# amplifier__6_1_Channel_v0001.net
KiCad netlist of a schematic drawn in EAGLE
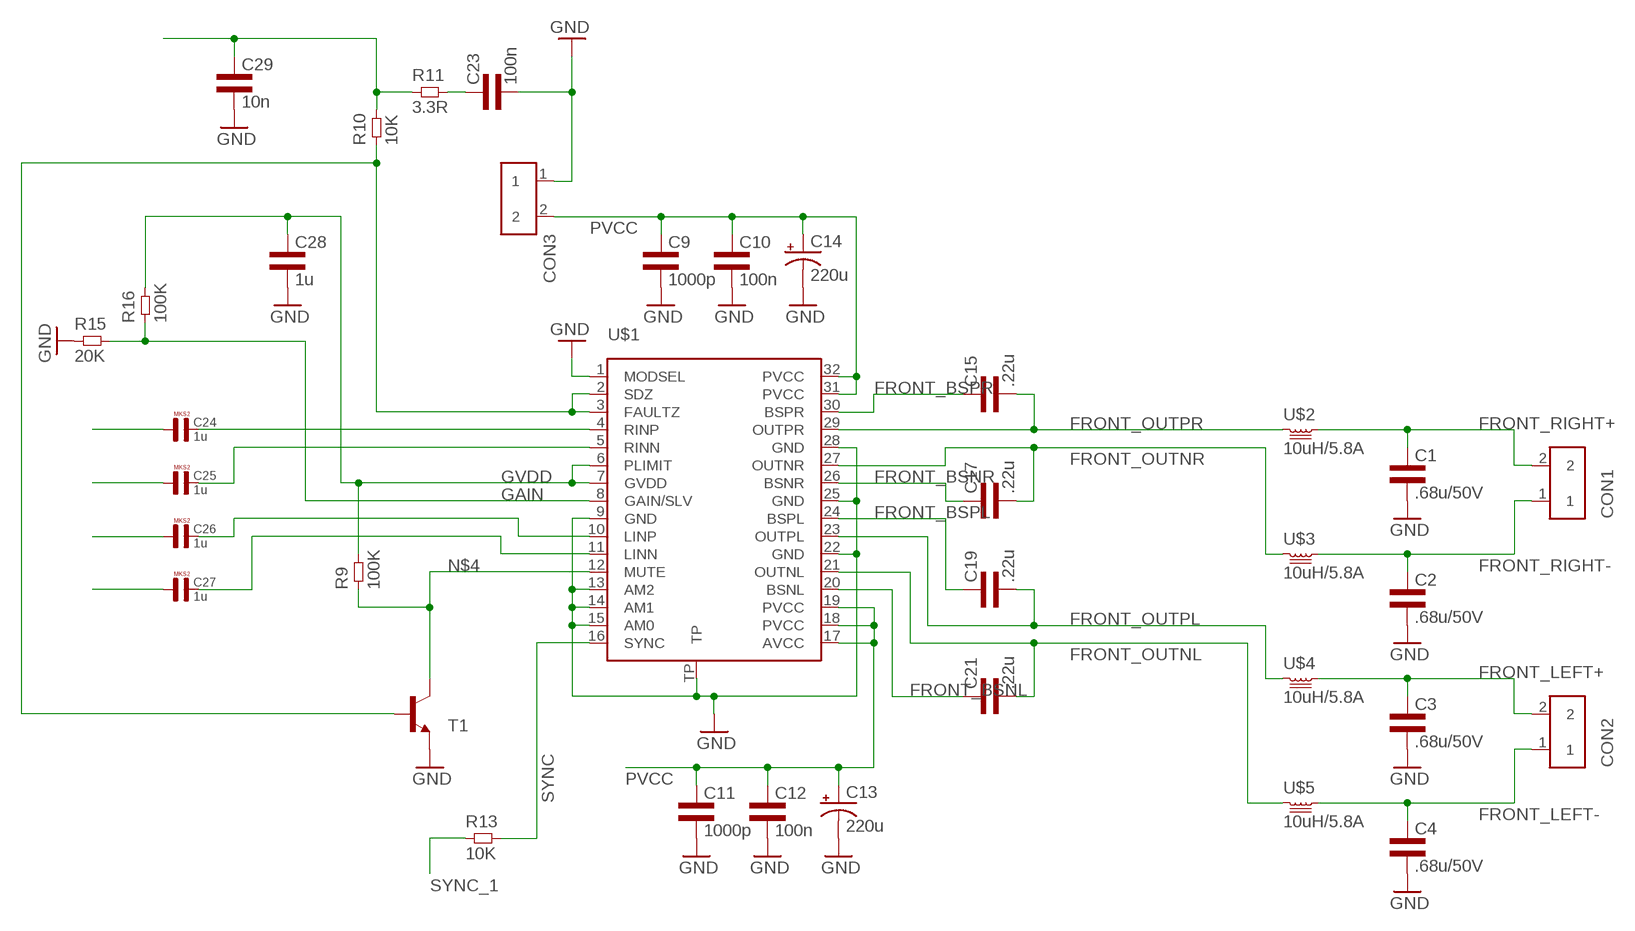
[diagram p0: schematic, sheet 1]
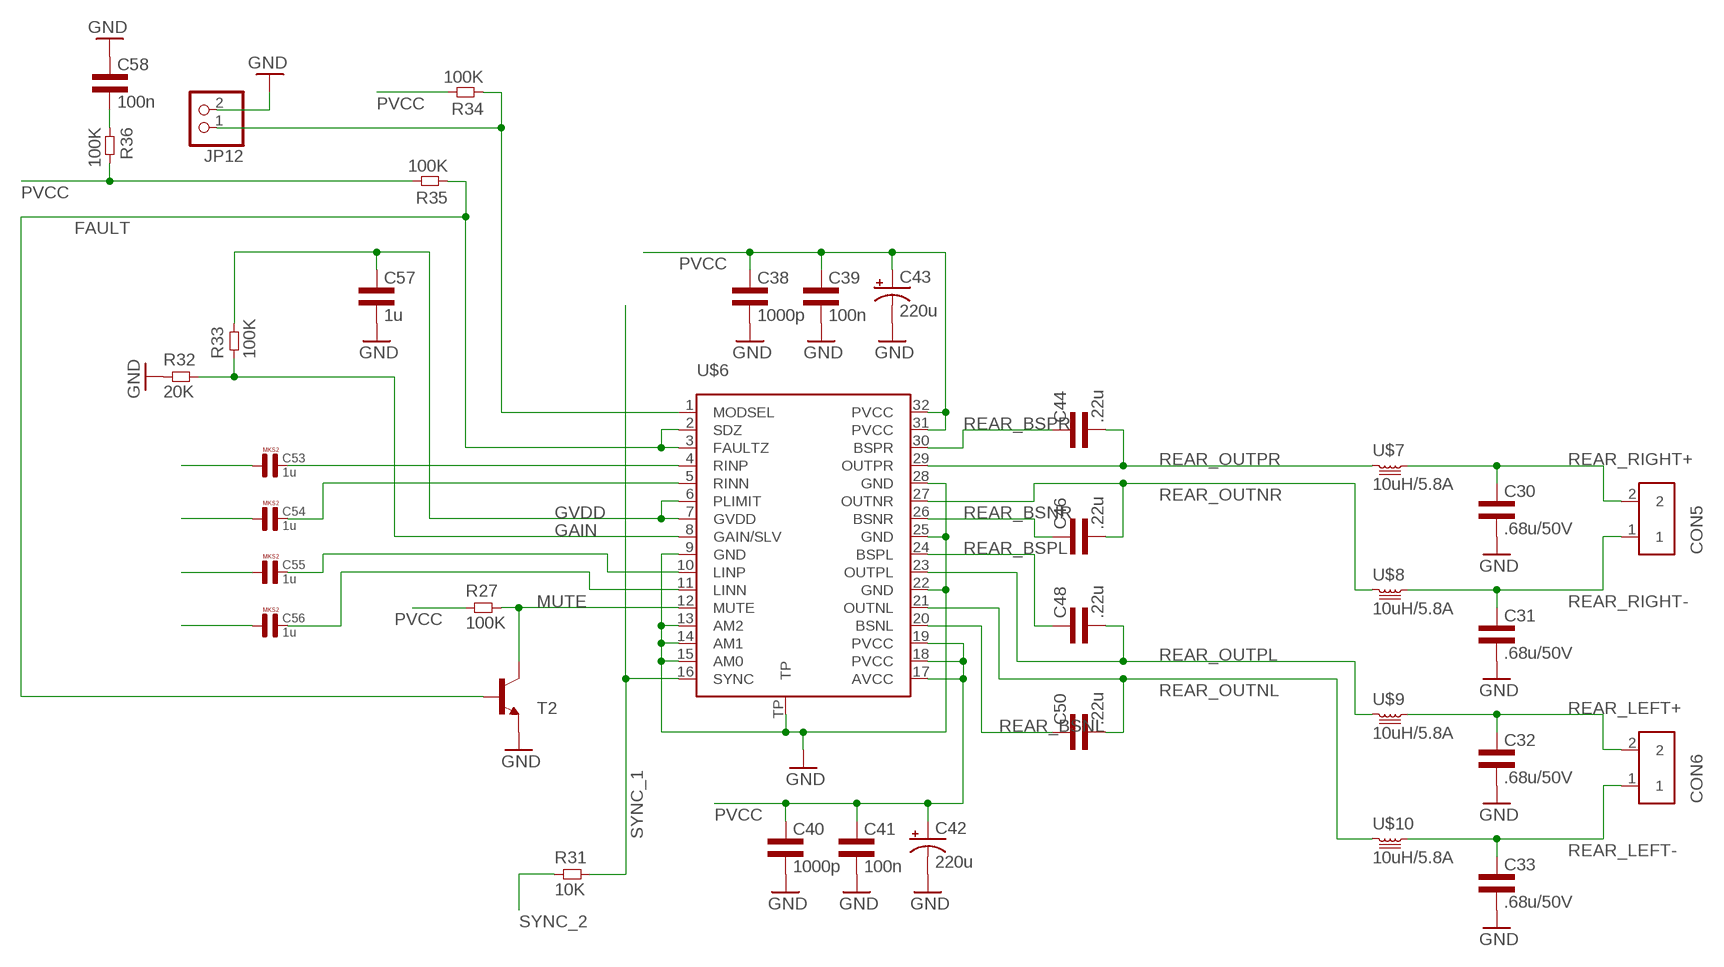
[diagram p1: schematic, sheet 2]
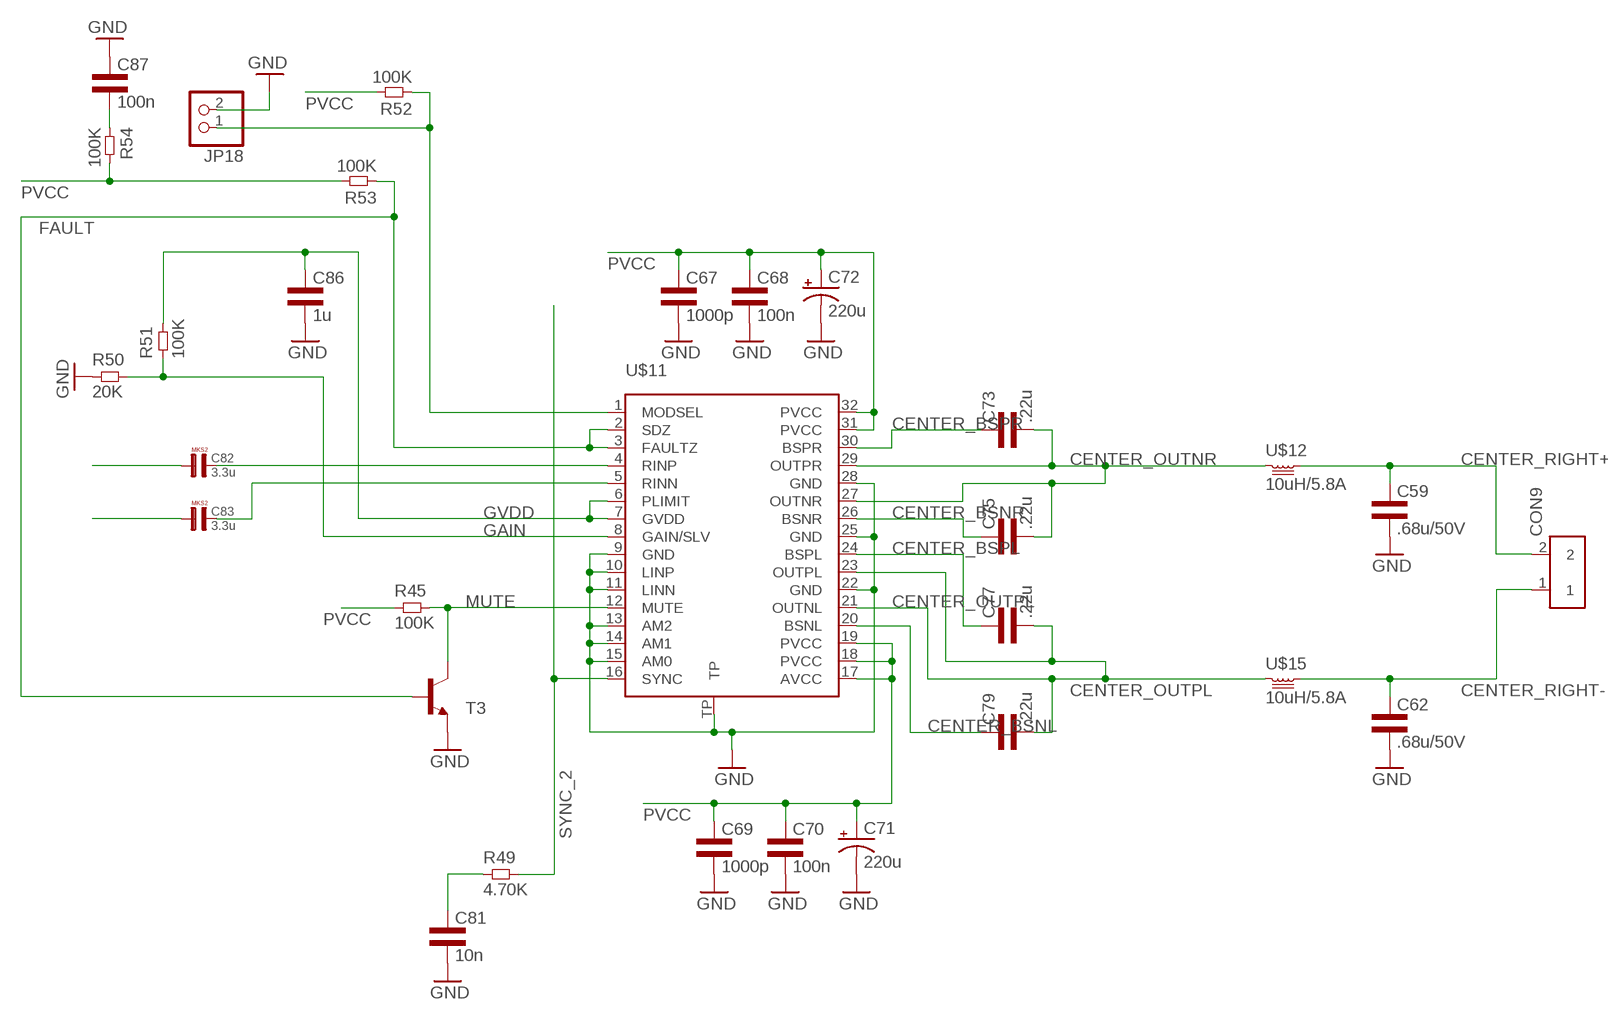
[diagram p2: schematic, sheet 3]

(export (version "E")
  (design (tool "Eeschema 10.0.6"))
  (components
    (comp (ref "C30")
      (value ".68u/50V")
      (footprint "eagle-import:1206L3")
      (libsource (lib "eagle-import") (part "CAP1206L3"))
    )
    (comp (ref "C31")
      (value ".68u/50V")
      (footprint "eagle-import:1206L3")
      (libsource (lib "eagle-import") (part "CAP1206L3"))
    )
    (comp (ref "C32")
      (value ".68u/50V")
      (footprint "eagle-import:1206L3")
      (libsource (lib "eagle-import") (part "CAP1206L3"))
    )
    (comp (ref "C33")
      (value ".68u/50V")
      (footprint "eagle-import:1206L3")
      (libsource (lib "eagle-import") (part "CAP1206L3"))
    )
    (comp (ref "C38")
      (value "1000p")
      (footprint "eagle-import:0603L3")
      (libsource (lib "eagle-import") (part "CAP0603L3"))
    )
    (comp (ref "C39")
      (value "100n")
      (footprint "eagle-import:0603L3")
      (libsource (lib "eagle-import") (part "CAP0603L3"))
    )
    (comp (ref "C40")
      (value "1000p")
      (footprint "eagle-import:0603L3")
      (libsource (lib "eagle-import") (part "CAP0603L3"))
    )
    (comp (ref "C41")
      (value "100n")
      (footprint "eagle-import:0603L3")
      (libsource (lib "eagle-import") (part "CAP0603L3"))
    )
    (comp (ref "C42")
      (value "220u")
      (footprint "eagle-import:PANASONIC_G")
      (libsource (lib "eagle-import") (part "CPOL-USG"))
    )
    (comp (ref "C43")
      (value "220u")
      (footprint "eagle-import:PANASONIC_G")
      (libsource (lib "eagle-import") (part "CPOL-USG"))
    )
    (comp (ref "C44")
      (value ".22u")
      (footprint "eagle-import:0603L3")
      (libsource (lib "eagle-import") (part "CAP0603L3"))
    )
    (comp (ref "C46")
      (value ".22u")
      (footprint "eagle-import:0603L3")
      (libsource (lib "eagle-import") (part "CAP0603L3"))
    )
    (comp (ref "C48")
      (value ".22u")
      (footprint "eagle-import:0603L3")
      (libsource (lib "eagle-import") (part "CAP0603L3"))
    )
    (comp (ref "C50")
      (value ".22u")
      (footprint "eagle-import:0603L3")
      (libsource (lib "eagle-import") (part "CAP0603L3"))
    )
    (comp (ref "C53")
      (value "1u")
      (footprint "eagle-import:R5B8K5")
      (libsource (lib "eagle-import") (part "3,3µF"))
    )
    (comp (ref "C54")
      (value "1u")
      (footprint "eagle-import:R5B8K5")
      (libsource (lib "eagle-import") (part "3,3µF"))
    )
    (comp (ref "C55")
      (value "1u")
      (footprint "eagle-import:R5B8K5")
      (libsource (lib "eagle-import") (part "3,3µF"))
    )
    (comp (ref "C56")
      (value "1u")
      (footprint "eagle-import:R5B8K5")
      (libsource (lib "eagle-import") (part "3,3µF"))
    )
    (comp (ref "C57")
      (value "1u")
      (footprint "eagle-import:0603L3")
      (libsource (lib "eagle-import") (part "CAP0603L3"))
    )
    (comp (ref "C58")
      (value "100n")
      (footprint "eagle-import:0603L3")
      (libsource (lib "eagle-import") (part "CAP0603L3"))
    )
    (comp (ref "CON5")
      (value "TERM_BLOCK_2")
      (footprint "eagle-import:TERM_BLOCK_2")
      (libsource (lib "eagle-import") (part "TERM_BLOCK_2"))
    )
    (comp (ref "CON6")
      (value "TERM_BLOCK_2")
      (footprint "eagle-import:TERM_BLOCK_2")
      (libsource (lib "eagle-import") (part "TERM_BLOCK_2"))
    )
    (comp (ref "JP12")
      (value "PINHD-1X2")
      (footprint "eagle-import:1X02")
      (libsource (lib "eagle-import") (part "PINHD-1X2"))
    )
    (comp (ref "R27")
      (value "100K")
      (footprint "eagle-import:0603L3")
      (libsource (lib "eagle-import") (part "RES0603L3"))
    )
    (comp (ref "R31")
      (value "10K")
      (footprint "eagle-import:0603L3")
      (libsource (lib "eagle-import") (part "RES0603L3"))
    )
    (comp (ref "R32")
      (value "20K")
      (footprint "eagle-import:0603L3")
      (libsource (lib "eagle-import") (part "RES0603L3"))
    )
    (comp (ref "R33")
      (value "100K")
      (footprint "eagle-import:0603L3")
      (libsource (lib "eagle-import") (part "RES0603L3"))
    )
    (comp (ref "R34")
      (value "100K")
      (footprint "eagle-import:0603L3")
      (libsource (lib "eagle-import") (part "RES0603L3"))
    )
    (comp (ref "R35")
      (value "100K")
      (footprint "eagle-import:0603L3")
      (libsource (lib "eagle-import") (part "RES0603L3"))
    )
    (comp (ref "R36")
      (value "100K")
      (footprint "eagle-import:0603L3")
      (libsource (lib "eagle-import") (part "RES0603L3"))
    )
    (comp (ref "T2")
      (value "TRANSISTOR_MMBT2222ALT1-NPN-SOT23-BEC")
      (footprint "eagle-import:TRANSISTOR_SOT23-BEC")
      (libsource (lib "eagle-import") (part "TRANSISTOR_-NPN-SOT23-BECMMBT2222ALT1"))
    )
    (comp (ref "U$6")
      (value "TPA3116")
      (footprint "eagle-import:R-PDSO-32")
      (libsource (lib "eagle-import") (part "TPA3116"))
    )
    (comp (ref "U$7")
      (value "10uH/5.8A")
      (footprint "eagle-import:DR127")
      (libsource (lib "eagle-import") (part "INDUCTORDR127"))
    )
    (comp (ref "U$8")
      (value "10uH/5.8A")
      (footprint "eagle-import:DR127")
      (libsource (lib "eagle-import") (part "INDUCTORDR127"))
    )
    (comp (ref "U$9")
      (value "10uH/5.8A")
      (footprint "eagle-import:DR127")
      (libsource (lib "eagle-import") (part "INDUCTORDR127"))
    )
    (comp (ref "U$10")
      (value "10uH/5.8A")
      (footprint "eagle-import:DR127")
      (libsource (lib "eagle-import") (part "INDUCTORDR127"))
    )
    (comp (ref "C59")
      (value ".68u/50V")
      (footprint "eagle-import:1206L3")
      (libsource (lib "eagle-import") (part "CAP1206L3"))
    )
    (comp (ref "C62")
      (value ".68u/50V")
      (footprint "eagle-import:1206L3")
      (libsource (lib "eagle-import") (part "CAP1206L3"))
    )
    (comp (ref "C67")
      (value "1000p")
      (footprint "eagle-import:0603L3")
      (libsource (lib "eagle-import") (part "CAP0603L3"))
    )
    (comp (ref "C68")
      (value "100n")
      (footprint "eagle-import:0603L3")
      (libsource (lib "eagle-import") (part "CAP0603L3"))
    )
    (comp (ref "C69")
      (value "1000p")
      (footprint "eagle-import:0603L3")
      (libsource (lib "eagle-import") (part "CAP0603L3"))
    )
    (comp (ref "C70")
      (value "100n")
      (footprint "eagle-import:0603L3")
      (libsource (lib "eagle-import") (part "CAP0603L3"))
    )
    (comp (ref "C71")
      (value "220u")
      (footprint "eagle-import:PANASONIC_G")
      (libsource (lib "eagle-import") (part "CPOL-USG"))
    )
    (comp (ref "C72")
      (value "220u")
      (footprint "eagle-import:PANASONIC_G")
      (libsource (lib "eagle-import") (part "CPOL-USG"))
    )
    (comp (ref "C73")
      (value ".22u")
      (footprint "eagle-import:0603L3")
      (libsource (lib "eagle-import") (part "CAP0603L3"))
    )
    (comp (ref "C75")
      (value ".22u")
      (footprint "eagle-import:0603L3")
      (libsource (lib "eagle-import") (part "CAP0603L3"))
    )
    (comp (ref "C77")
      (value ".22u")
      (footprint "eagle-import:0603L3")
      (libsource (lib "eagle-import") (part "CAP0603L3"))
    )
    (comp (ref "C79")
      (value ".22u")
      (footprint "eagle-import:0603L3")
      (libsource (lib "eagle-import") (part "CAP0603L3"))
    )
    (comp (ref "C81")
      (value "10n")
      (footprint "eagle-import:0603L3")
      (libsource (lib "eagle-import") (part "CAP0603L3"))
    )
    (comp (ref "C82")
      (value "3.3u")
      (footprint "eagle-import:R5B8K5")
      (libsource (lib "eagle-import") (part "3,3µF"))
    )
    (comp (ref "C83")
      (value "3.3u")
      (footprint "eagle-import:R5B8K5")
      (libsource (lib "eagle-import") (part "3,3µF"))
    )
    (comp (ref "C86")
      (value "1u")
      (footprint "eagle-import:0603L3")
      (libsource (lib "eagle-import") (part "CAP0603L3"))
    )
    (comp (ref "C87")
      (value "100n")
      (footprint "eagle-import:0603L3")
      (libsource (lib "eagle-import") (part "CAP0603L3"))
    )
    (comp (ref "CON9")
      (value "TERM_BLOCK_2")
      (footprint "eagle-import:TERM_BLOCK_2")
      (libsource (lib "eagle-import") (part "TERM_BLOCK_2"))
    )
    (comp (ref "JP18")
      (value "PINHD-1X2")
      (footprint "eagle-import:1X02")
      (libsource (lib "eagle-import") (part "PINHD-1X2"))
    )
    (comp (ref "R45")
      (value "100K")
      (footprint "eagle-import:0603L3")
      (libsource (lib "eagle-import") (part "RES0603L3"))
    )
    (comp (ref "R49")
      (value "4.70K")
      (footprint "eagle-import:0603L3")
      (libsource (lib "eagle-import") (part "RES0603L3"))
    )
    (comp (ref "R50")
      (value "20K")
      (footprint "eagle-import:0603L3")
      (libsource (lib "eagle-import") (part "RES0603L3"))
    )
    (comp (ref "R51")
      (value "100K")
      (footprint "eagle-import:0603L3")
      (libsource (lib "eagle-import") (part "RES0603L3"))
    )
    (comp (ref "R52")
      (value "100K")
      (footprint "eagle-import:0603L3")
      (libsource (lib "eagle-import") (part "RES0603L3"))
    )
    (comp (ref "R53")
      (value "100K")
      (footprint "eagle-import:0603L3")
      (libsource (lib "eagle-import") (part "RES0603L3"))
    )
    (comp (ref "R54")
      (value "100K")
      (footprint "eagle-import:0603L3")
      (libsource (lib "eagle-import") (part "RES0603L3"))
    )
    (comp (ref "T3")
      (value "TRANSISTOR_MMBT2222ALT1-NPN-SOT23-BEC")
      (footprint "eagle-import:TRANSISTOR_SOT23-BEC")
      (libsource (lib "eagle-import") (part "TRANSISTOR_-NPN-SOT23-BECMMBT2222ALT1"))
    )
    (comp (ref "U$11")
      (value "TPA3116")
      (footprint "eagle-import:R-PDSO-32")
      (libsource (lib "eagle-import") (part "TPA3116"))
    )
    (comp (ref "U$12")
      (value "10uH/5.8A")
      (footprint "eagle-import:DR127")
      (libsource (lib "eagle-import") (part "INDUCTORDR127"))
    )
    (comp (ref "U$15")
      (value "10uH/5.8A")
      (footprint "eagle-import:DR127")
      (libsource (lib "eagle-import") (part "INDUCTORDR127"))
    )
    (comp (ref "C1")
      (value ".68u/50V")
      (footprint "eagle-import:1206L3")
      (libsource (lib "eagle-import") (part "CAP1206L3"))
    )
    (comp (ref "C2")
      (value ".68u/50V")
      (footprint "eagle-import:1206L3")
      (libsource (lib "eagle-import") (part "CAP1206L3"))
    )
    (comp (ref "C3")
      (value ".68u/50V")
      (footprint "eagle-import:1206L3")
      (libsource (lib "eagle-import") (part "CAP1206L3"))
    )
    (comp (ref "C4")
      (value ".68u/50V")
      (footprint "eagle-import:1206L3")
      (libsource (lib "eagle-import") (part "CAP1206L3"))
    )
    (comp (ref "C9")
      (value "1000p")
      (footprint "eagle-import:0603L3")
      (libsource (lib "eagle-import") (part "CAP0603L3"))
    )
    (comp (ref "C10")
      (value "100n")
      (footprint "eagle-import:0603L3")
      (libsource (lib "eagle-import") (part "CAP0603L3"))
    )
    (comp (ref "C11")
      (value "1000p")
      (footprint "eagle-import:0603L3")
      (libsource (lib "eagle-import") (part "CAP0603L3"))
    )
    (comp (ref "C12")
      (value "100n")
      (footprint "eagle-import:0603L3")
      (libsource (lib "eagle-import") (part "CAP0603L3"))
    )
    (comp (ref "C13")
      (value "220u")
      (footprint "eagle-import:PANASONIC_G")
      (libsource (lib "eagle-import") (part "CPOL-USG"))
    )
    (comp (ref "C14")
      (value "220u")
      (footprint "eagle-import:PANASONIC_G")
      (libsource (lib "eagle-import") (part "CPOL-USG"))
    )
    (comp (ref "C15")
      (value ".22u")
      (footprint "eagle-import:0603L3")
      (libsource (lib "eagle-import") (part "CAP0603L3"))
    )
    (comp (ref "C17")
      (value ".22u")
      (footprint "eagle-import:0603L3")
      (libsource (lib "eagle-import") (part "CAP0603L3"))
    )
    (comp (ref "C19")
      (value ".22u")
      (footprint "eagle-import:0603L3")
      (libsource (lib "eagle-import") (part "CAP0603L3"))
    )
    (comp (ref "C21")
      (value ".22u")
      (footprint "eagle-import:0603L3")
      (libsource (lib "eagle-import") (part "CAP0603L3"))
    )
    (comp (ref "C23")
      (value "100n")
      (footprint "eagle-import:0603L3")
      (libsource (lib "eagle-import") (part "CAP0603L3"))
    )
    (comp (ref "C24")
      (value "1u")
      (footprint "eagle-import:R5B8K5")
      (libsource (lib "eagle-import") (part "3,3µF"))
    )
    (comp (ref "C25")
      (value "1u")
      (footprint "eagle-import:R5B8K5")
      (libsource (lib "eagle-import") (part "3,3µF"))
    )
    (comp (ref "C26")
      (value "1u")
      (footprint "eagle-import:R5B8K5")
      (libsource (lib "eagle-import") (part "3,3µF"))
    )
    (comp (ref "C27")
      (value "1u")
      (footprint "eagle-import:R5B8K5")
      (libsource (lib "eagle-import") (part "3,3µF"))
    )
    (comp (ref "C28")
      (value "1u")
      (footprint "eagle-import:0603L3")
      (libsource (lib "eagle-import") (part "CAP0603L3"))
    )
    (comp (ref "C29")
      (value "10n")
      (footprint "eagle-import:0603L3")
      (libsource (lib "eagle-import") (part "CAP0603L3"))
    )
    (comp (ref "CON1")
      (value "TERM_BLOCK_2")
      (footprint "eagle-import:TERM_BLOCK_2")
      (libsource (lib "eagle-import") (part "TERM_BLOCK_2"))
    )
    (comp (ref "CON2")
      (value "TERM_BLOCK_2")
      (footprint "eagle-import:TERM_BLOCK_2")
      (libsource (lib "eagle-import") (part "TERM_BLOCK_2"))
    )
    (comp (ref "CON3")
      (value "TERM_BLOCK_2")
      (footprint "eagle-import:TERM_BLOCK_2")
      (libsource (lib "eagle-import") (part "TERM_BLOCK_2"))
    )
    (comp (ref "R9")
      (value "100K")
      (footprint "eagle-import:0603L3")
      (libsource (lib "eagle-import") (part "RES0603L3"))
    )
    (comp (ref "R10")
      (value "10K")
      (footprint "eagle-import:0603L3")
      (libsource (lib "eagle-import") (part "RES0603L3"))
    )
    (comp (ref "R11")
      (value "3.3R")
      (footprint "eagle-import:0603L3")
      (libsource (lib "eagle-import") (part "RES0603L3"))
    )
    (comp (ref "R13")
      (value "10K")
      (footprint "eagle-import:0603L3")
      (libsource (lib "eagle-import") (part "RES0603L3"))
    )
    (comp (ref "R15")
      (value "20K")
      (footprint "eagle-import:0603L3")
      (libsource (lib "eagle-import") (part "RES0603L3"))
    )
    (comp (ref "R16")
      (value "100K")
      (footprint "eagle-import:0603L3")
      (libsource (lib "eagle-import") (part "RES0603L3"))
    )
    (comp (ref "T1")
      (value "TRANSISTOR_MMBT2222ALT1-NPN-SOT23-BEC")
      (footprint "eagle-import:TRANSISTOR_SOT23-BEC")
      (libsource (lib "eagle-import") (part "TRANSISTOR_-NPN-SOT23-BECMMBT2222ALT1"))
    )
    (comp (ref "U$1")
      (value "TPA3116")
      (footprint "eagle-import:R-PDSO-32")
      (libsource (lib "eagle-import") (part "TPA3116"))
    )
    (comp (ref "U$2")
      (value "10uH/5.8A")
      (footprint "eagle-import:DR127")
      (libsource (lib "eagle-import") (part "INDUCTORDR127"))
    )
    (comp (ref "U$3")
      (value "10uH/5.8A")
      (footprint "eagle-import:DR127")
      (libsource (lib "eagle-import") (part "INDUCTORDR127"))
    )
    (comp (ref "U$4")
      (value "10uH/5.8A")
      (footprint "eagle-import:DR127")
      (libsource (lib "eagle-import") (part "INDUCTORDR127"))
    )
    (comp (ref "U$5")
      (value "10uH/5.8A")
      (footprint "eagle-import:DR127")
      (libsource (lib "eagle-import") (part "INDUCTORDR127"))
    )
  )
  (nets
    (net (code "1") (name "CENTER_BSNL") (class "Default")
      (node (ref "C79") (pin "P$1") (pinfunction "1_P$1") (pintype "bidirectional"))
      (node (ref "U$11") (pin "20") (pinfunction "BSNL_20") (pintype "bidirectional"))
    )
    (net (code "2") (name "CENTER_BSNR") (class "Default")
      (node (ref "C75") (pin "P$1") (pinfunction "1_P$1") (pintype "bidirectional"))
      (node (ref "U$11") (pin "26") (pinfunction "BSNR_26") (pintype "bidirectional"))
    )
    (net (code "3") (name "CENTER_BSPL") (class "Default")
      (node (ref "C77") (pin "P$1") (pinfunction "1_P$1") (pintype "bidirectional"))
      (node (ref "U$11") (pin "24") (pinfunction "BSPL_24") (pintype "bidirectional"))
    )
    (net (code "4") (name "CENTER_BSPR") (class "Default")
      (node (ref "C73") (pin "P$1") (pinfunction "1_P$1") (pintype "bidirectional"))
      (node (ref "U$11") (pin "30") (pinfunction "BSPR_30") (pintype "bidirectional"))
    )
    (net (code "5") (name "CENTER_OUTNR") (class "Default")
      (node (ref "C73") (pin "P$2") (pinfunction "2_P$2") (pintype "bidirectional"))
      (node (ref "C75") (pin "P$2") (pinfunction "2_P$2") (pintype "bidirectional"))
      (node (ref "U$11") (pin "27") (pinfunction "OUTNR_27") (pintype "bidirectional"))
      (node (ref "U$11") (pin "29") (pinfunction "OUTPR_29") (pintype "bidirectional"))
      (node (ref "U$12") (pin "1") (pinfunction "1_1") (pintype "bidirectional"))
    )
    (net (code "6") (name "CENTER_OUTPL") (class "Default")
      (node (ref "C77") (pin "P$2") (pinfunction "2_P$2") (pintype "bidirectional"))
      (node (ref "C79") (pin "P$2") (pinfunction "2_P$2") (pintype "bidirectional"))
      (node (ref "U$11") (pin "21") (pinfunction "OUTNL_21") (pintype "bidirectional"))
      (node (ref "U$11") (pin "23") (pinfunction "OUTPL_23") (pintype "bidirectional"))
      (node (ref "U$15") (pin "1") (pinfunction "1_1") (pintype "bidirectional"))
    )
    (net (code "7") (name "CENTER_RIGHT+") (class "Default")
      (node (ref "C59") (pin "1") (pinfunction "1_1") (pintype "bidirectional"))
      (node (ref "CON9") (pin "2") (pinfunction "2_2") (pintype "bidirectional"))
      (node (ref "U$12") (pin "2") (pinfunction "2_2") (pintype "bidirectional"))
    )
    (net (code "8") (name "CENTER_RIGHT-") (class "Default")
      (node (ref "C62") (pin "1") (pinfunction "1_1") (pintype "bidirectional"))
      (node (ref "CON9") (pin "1") (pinfunction "1_1") (pintype "bidirectional"))
      (node (ref "U$15") (pin "2") (pinfunction "2_2") (pintype "bidirectional"))
    )
    (net (code "9") (name "FAULT") (class "Default")
      (node (ref "R35") (pin "P$1") (pinfunction "1_P$1") (pintype "bidirectional"))
      (node (ref "R53") (pin "P$1") (pinfunction "1_P$1") (pintype "bidirectional"))
      (node (ref "T2") (pin "B") (pinfunction "B_B") (pintype "passive"))
      (node (ref "T3") (pin "B") (pinfunction "B_B") (pintype "passive"))
      (node (ref "U$11") (pin "2") (pinfunction "SDZ_2") (pintype "bidirectional"))
      (node (ref "U$11") (pin "3") (pinfunction "FAULTZ_3") (pintype "bidirectional"))
      (node (ref "U$6") (pin "2") (pinfunction "SDZ_2") (pintype "bidirectional"))
      (node (ref "U$6") (pin "3") (pinfunction "FAULTZ_3") (pintype "bidirectional"))
    )
    (net (code "10") (name "FRONT_BSNL") (class "Default")
      (node (ref "C21") (pin "P$1") (pinfunction "1_P$1") (pintype "bidirectional"))
      (node (ref "U$1") (pin "20") (pinfunction "BSNL_20") (pintype "bidirectional"))
    )
    (net (code "11") (name "FRONT_BSNR") (class "Default")
      (node (ref "C17") (pin "P$1") (pinfunction "1_P$1") (pintype "bidirectional"))
      (node (ref "U$1") (pin "26") (pinfunction "BSNR_26") (pintype "bidirectional"))
    )
    (net (code "12") (name "FRONT_BSPL") (class "Default")
      (node (ref "C19") (pin "P$1") (pinfunction "1_P$1") (pintype "bidirectional"))
      (node (ref "U$1") (pin "24") (pinfunction "BSPL_24") (pintype "bidirectional"))
    )
    (net (code "13") (name "FRONT_BSPR") (class "Default")
      (node (ref "C15") (pin "P$1") (pinfunction "1_P$1") (pintype "bidirectional"))
      (node (ref "U$1") (pin "30") (pinfunction "BSPR_30") (pintype "bidirectional"))
    )
    (net (code "14") (name "FRONT_LEFT+") (class "Default")
      (node (ref "C3") (pin "1") (pinfunction "1_1") (pintype "bidirectional"))
      (node (ref "CON2") (pin "2") (pinfunction "2_2") (pintype "bidirectional"))
      (node (ref "U$4") (pin "2") (pinfunction "2_2") (pintype "bidirectional"))
    )
    (net (code "15") (name "FRONT_LEFT-") (class "Default")
      (node (ref "C4") (pin "1") (pinfunction "1_1") (pintype "bidirectional"))
      (node (ref "CON2") (pin "1") (pinfunction "1_1") (pintype "bidirectional"))
      (node (ref "U$5") (pin "2") (pinfunction "2_2") (pintype "bidirectional"))
    )
    (net (code "16") (name "FRONT_OUTNL") (class "Default")
      (node (ref "C21") (pin "P$2") (pinfunction "2_P$2") (pintype "bidirectional"))
      (node (ref "U$1") (pin "21") (pinfunction "OUTNL_21") (pintype "bidirectional"))
      (node (ref "U$5") (pin "1") (pinfunction "1_1") (pintype "bidirectional"))
    )
    (net (code "17") (name "FRONT_OUTNR") (class "Default")
      (node (ref "C17") (pin "P$2") (pinfunction "2_P$2") (pintype "bidirectional"))
      (node (ref "U$1") (pin "27") (pinfunction "OUTNR_27") (pintype "bidirectional"))
      (node (ref "U$3") (pin "1") (pinfunction "1_1") (pintype "bidirectional"))
    )
    (net (code "18") (name "FRONT_OUTPL") (class "Default")
      (node (ref "C19") (pin "P$2") (pinfunction "2_P$2") (pintype "bidirectional"))
      (node (ref "U$1") (pin "23") (pinfunction "OUTPL_23") (pintype "bidirectional"))
      (node (ref "U$4") (pin "1") (pinfunction "1_1") (pintype "bidirectional"))
    )
    (net (code "19") (name "FRONT_OUTPR") (class "Default")
      (node (ref "C15") (pin "P$2") (pinfunction "2_P$2") (pintype "bidirectional"))
      (node (ref "U$1") (pin "29") (pinfunction "OUTPR_29") (pintype "bidirectional"))
      (node (ref "U$2") (pin "1") (pinfunction "1_1") (pintype "bidirectional"))
    )
    (net (code "20") (name "FRONT_RIGHT+") (class "Default")
      (node (ref "C1") (pin "1") (pinfunction "1_1") (pintype "bidirectional"))
      (node (ref "CON1") (pin "2") (pinfunction "2_2") (pintype "bidirectional"))
      (node (ref "U$2") (pin "2") (pinfunction "2_2") (pintype "bidirectional"))
    )
    (net (code "21") (name "FRONT_RIGHT-") (class "Default")
      (node (ref "C2") (pin "1") (pinfunction "1_1") (pintype "bidirectional"))
      (node (ref "CON1") (pin "1") (pinfunction "1_1") (pintype "bidirectional"))
      (node (ref "U$3") (pin "2") (pinfunction "2_2") (pintype "bidirectional"))
    )
    (net (code "22") (name "GAIN") (class "Default")
      (node (ref "R15") (pin "P$2") (pinfunction "2_P$2") (pintype "bidirectional"))
      (node (ref "R16") (pin "P$1") (pinfunction "1_P$1") (pintype "bidirectional"))
      (node (ref "R32") (pin "P$2") (pinfunction "2_P$2") (pintype "bidirectional"))
      (node (ref "R33") (pin "P$1") (pinfunction "1_P$1") (pintype "bidirectional"))
      (node (ref "R50") (pin "P$2") (pinfunction "2_P$2") (pintype "bidirectional"))
      (node (ref "R51") (pin "P$1") (pinfunction "1_P$1") (pintype "bidirectional"))
      (node (ref "U$1") (pin "8") (pinfunction "GAIN/SLV_8") (pintype "bidirectional"))
      (node (ref "U$11") (pin "8") (pinfunction "GAIN/SLV_8") (pintype "bidirectional"))
      (node (ref "U$6") (pin "8") (pinfunction "GAIN/SLV_8") (pintype "bidirectional"))
    )
    (net (code "23") (name "GND") (class "Default")
      (node (ref "C1") (pin "2") (pinfunction "2_2") (pintype "bidirectional"))
      (node (ref "C10") (pin "P$2") (pinfunction "2_P$2") (pintype "bidirectional"))
      (node (ref "C11") (pin "P$2") (pinfunction "2_P$2") (pintype "bidirectional"))
      (node (ref "C12") (pin "P$2") (pinfunction "2_P$2") (pintype "bidirectional"))
      (node (ref "C13") (pin "-") (pinfunction "-_-") (pintype "passive"))
      (node (ref "C14") (pin "-") (pinfunction "-_-") (pintype "passive"))
      (node (ref "C2") (pin "2") (pinfunction "2_2") (pintype "bidirectional"))
      (node (ref "C23") (pin "P$2") (pinfunction "2_P$2") (pintype "bidirectional"))
      (node (ref "C28") (pin "P$2") (pinfunction "2_P$2") (pintype "bidirectional"))
      (node (ref "C29") (pin "P$2") (pinfunction "2_P$2") (pintype "bidirectional"))
      (node (ref "C3") (pin "2") (pinfunction "2_2") (pintype "bidirectional"))
      (node (ref "C30") (pin "2") (pinfunction "2_2") (pintype "bidirectional"))
      (node (ref "C31") (pin "2") (pinfunction "2_2") (pintype "bidirectional"))
      (node (ref "C32") (pin "2") (pinfunction "2_2") (pintype "bidirectional"))
      (node (ref "C33") (pin "2") (pinfunction "2_2") (pintype "bidirectional"))
      (node (ref "C38") (pin "P$2") (pinfunction "2_P$2") (pintype "bidirectional"))
      (node (ref "C39") (pin "P$2") (pinfunction "2_P$2") (pintype "bidirectional"))
      (node (ref "C4") (pin "2") (pinfunction "2_2") (pintype "bidirectional"))
      (node (ref "C40") (pin "P$2") (pinfunction "2_P$2") (pintype "bidirectional"))
      (node (ref "C41") (pin "P$2") (pinfunction "2_P$2") (pintype "bidirectional"))
      (node (ref "C42") (pin "-") (pinfunction "-_-") (pintype "passive"))
      (node (ref "C43") (pin "-") (pinfunction "-_-") (pintype "passive"))
      (node (ref "C57") (pin "P$2") (pinfunction "2_P$2") (pintype "bidirectional"))
      (node (ref "C58") (pin "P$1") (pinfunction "1_P$1") (pintype "bidirectional"))
      (node (ref "C59") (pin "2") (pinfunction "2_2") (pintype "bidirectional"))
      (node (ref "C62") (pin "2") (pinfunction "2_2") (pintype "bidirectional"))
      (node (ref "C67") (pin "P$2") (pinfunction "2_P$2") (pintype "bidirectional"))
      (node (ref "C68") (pin "P$2") (pinfunction "2_P$2") (pintype "bidirectional"))
      (node (ref "C69") (pin "P$2") (pinfunction "2_P$2") (pintype "bidirectional"))
      (node (ref "C70") (pin "P$2") (pinfunction "2_P$2") (pintype "bidirectional"))
      (node (ref "C71") (pin "-") (pinfunction "-_-") (pintype "passive"))
      (node (ref "C72") (pin "-") (pinfunction "-_-") (pintype "passive"))
      (node (ref "C81") (pin "P$2") (pinfunction "2_P$2") (pintype "bidirectional"))
      (node (ref "C86") (pin "P$2") (pinfunction "2_P$2") (pintype "bidirectional"))
      (node (ref "C87") (pin "P$1") (pinfunction "1_P$1") (pintype "bidirectional"))
      (node (ref "C9") (pin "P$2") (pinfunction "2_P$2") (pintype "bidirectional"))
      (node (ref "CON3") (pin "1") (pinfunction "1_1") (pintype "bidirectional"))
      (node (ref "JP12") (pin "2") (pinfunction "2_2") (pintype "passive"))
      (node (ref "JP18") (pin "2") (pinfunction "2_2") (pintype "passive"))
      (node (ref "R15") (pin "P$1") (pinfunction "1_P$1") (pintype "bidirectional"))
      (node (ref "R32") (pin "P$1") (pinfunction "1_P$1") (pintype "bidirectional"))
      (node (ref "R50") (pin "P$1") (pinfunction "1_P$1") (pintype "bidirectional"))
      (node (ref "T1") (pin "E") (pinfunction "E_E") (pintype "passive"))
      (node (ref "T2") (pin "E") (pinfunction "E_E") (pintype "passive"))
      (node (ref "T3") (pin "E") (pinfunction "E_E") (pintype "passive"))
      (node (ref "U$1") (pin "1") (pinfunction "MODSEL_1") (pintype "bidirectional"))
      (node (ref "U$1") (pin "13") (pinfunction "AM2_13") (pintype "bidirectional"))
      (node (ref "U$1") (pin "14") (pinfunction "AM1_14") (pintype "bidirectional"))
      (node (ref "U$1") (pin "15") (pinfunction "AM0_15") (pintype "bidirectional"))
      (node (ref "U$1") (pin "22") (pinfunction "GND_22") (pintype "bidirectional"))
      (node (ref "U$1") (pin "25") (pinfunction "GND_25") (pintype "bidirectional"))
      (node (ref "U$1") (pin "28") (pinfunction "GND_28") (pintype "bidirectional"))
      (node (ref "U$1") (pin "9") (pinfunction "GND_9") (pintype "bidirectional"))
      (node (ref "U$1") (pin "TP") (pinfunction "TP_TP") (pintype "bidirectional"))
      (node (ref "U$11") (pin "10") (pinfunction "LINP_10") (pintype "bidirectional"))
      (node (ref "U$11") (pin "11") (pinfunction "LINN_11") (pintype "bidirectional"))
      (node (ref "U$11") (pin "13") (pinfunction "AM2_13") (pintype "bidirectional"))
      (node (ref "U$11") (pin "14") (pinfunction "AM1_14") (pintype "bidirectional"))
      (node (ref "U$11") (pin "15") (pinfunction "AM0_15") (pintype "bidirectional"))
      (node (ref "U$11") (pin "22") (pinfunction "GND_22") (pintype "bidirectional"))
      (node (ref "U$11") (pin "25") (pinfunction "GND_25") (pintype "bidirectional"))
      (node (ref "U$11") (pin "28") (pinfunction "GND_28") (pintype "bidirectional"))
      (node (ref "U$11") (pin "9") (pinfunction "GND_9") (pintype "bidirectional"))
      (node (ref "U$11") (pin "TP") (pinfunction "TP_TP") (pintype "bidirectional"))
      (node (ref "U$6") (pin "13") (pinfunction "AM2_13") (pintype "bidirectional"))
      (node (ref "U$6") (pin "14") (pinfunction "AM1_14") (pintype "bidirectional"))
      (node (ref "U$6") (pin "15") (pinfunction "AM0_15") (pintype "bidirectional"))
      (node (ref "U$6") (pin "22") (pinfunction "GND_22") (pintype "bidirectional"))
      (node (ref "U$6") (pin "25") (pinfunction "GND_25") (pintype "bidirectional"))
      (node (ref "U$6") (pin "28") (pinfunction "GND_28") (pintype "bidirectional"))
      (node (ref "U$6") (pin "9") (pinfunction "GND_9") (pintype "bidirectional"))
      (node (ref "U$6") (pin "TP") (pinfunction "TP_TP") (pintype "bidirectional"))
    )
    (net (code "24") (name "GVDD") (class "Default")
      (node (ref "C28") (pin "P$1") (pinfunction "1_P$1") (pintype "bidirectional"))
      (node (ref "C57") (pin "P$1") (pinfunction "1_P$1") (pintype "bidirectional"))
      (node (ref "C86") (pin "P$1") (pinfunction "1_P$1") (pintype "bidirectional"))
      (node (ref "R16") (pin "P$2") (pinfunction "2_P$2") (pintype "bidirectional"))
      (node (ref "R33") (pin "P$2") (pinfunction "2_P$2") (pintype "bidirectional"))
      (node (ref "R51") (pin "P$2") (pinfunction "2_P$2") (pintype "bidirectional"))
      (node (ref "R9") (pin "P$2") (pinfunction "2_P$2") (pintype "bidirectional"))
      (node (ref "U$1") (pin "6") (pinfunction "PLIMIT_6") (pintype "bidirectional"))
      (node (ref "U$1") (pin "7") (pinfunction "GVDD_7") (pintype "bidirectional"))
      (node (ref "U$11") (pin "6") (pinfunction "PLIMIT_6") (pintype "bidirectional"))
      (node (ref "U$11") (pin "7") (pinfunction "GVDD_7") (pintype "bidirectional"))
      (node (ref "U$6") (pin "6") (pinfunction "PLIMIT_6") (pintype "bidirectional"))
      (node (ref "U$6") (pin "7") (pinfunction "GVDD_7") (pintype "bidirectional"))
    )
    (net (code "25") (name "MUTE") (class "Default")
      (node (ref "R10") (pin "P$1") (pinfunction "1_P$1") (pintype "bidirectional"))
      (node (ref "R27") (pin "P$2") (pinfunction "2_P$2") (pintype "bidirectional"))
      (node (ref "R45") (pin "P$2") (pinfunction "2_P$2") (pintype "bidirectional"))
      (node (ref "T1") (pin "B") (pinfunction "B_B") (pintype "passive"))
      (node (ref "T2") (pin "C") (pinfunction "C_C") (pintype "passive"))
      (node (ref "T3") (pin "C") (pinfunction "C_C") (pintype "passive"))
      (node (ref "U$1") (pin "2") (pinfunction "SDZ_2") (pintype "bidirectional"))
      (node (ref "U$1") (pin "3") (pinfunction "FAULTZ_3") (pintype "bidirectional"))
      (node (ref "U$11") (pin "12") (pinfunction "MUTE_12") (pintype "bidirectional"))
      (node (ref "U$6") (pin "12") (pinfunction "MUTE_12") (pintype "bidirectional"))
    )
    (net (code "26") (name "N$4") (class "Default")
      (node (ref "R9") (pin "P$1") (pinfunction "1_P$1") (pintype "bidirectional"))
      (node (ref "T1") (pin "C") (pinfunction "C_C") (pintype "passive"))
      (node (ref "U$1") (pin "12") (pinfunction "MUTE_12") (pintype "bidirectional"))
    )
    (net (code "27") (name "Net-(C23-1)") (class "Default")
      (node (ref "C23") (pin "P$1") (pinfunction "1_P$1") (pintype "bidirectional"))
      (node (ref "R11") (pin "P$2") (pinfunction "2_P$2") (pintype "bidirectional"))
    )
    (net (code "28") (name "Net-(C29-1)") (class "Default")
      (node (ref "C29") (pin "P$1") (pinfunction "1_P$1") (pintype "bidirectional"))
      (node (ref "R10") (pin "P$2") (pinfunction "2_P$2") (pintype "bidirectional"))
      (node (ref "R11") (pin "P$1") (pinfunction "1_P$1") (pintype "bidirectional"))
    )
    (net (code "29") (name "Net-(C58-2)") (class "Default")
      (node (ref "C58") (pin "P$2") (pinfunction "2_P$2") (pintype "bidirectional"))
      (node (ref "R36") (pin "P$1") (pinfunction "1_P$1") (pintype "bidirectional"))
    )
    (net (code "30") (name "Net-(C81-1)") (class "Default")
      (node (ref "C81") (pin "P$1") (pinfunction "1_P$1") (pintype "bidirectional"))
      (node (ref "R49") (pin "P$1") (pinfunction "1_P$1") (pintype "bidirectional"))
    )
    (net (code "31") (name "Net-(C87-2)") (class "Default")
      (node (ref "C87") (pin "P$2") (pinfunction "2_P$2") (pintype "bidirectional"))
      (node (ref "R54") (pin "P$1") (pinfunction "1_P$1") (pintype "bidirectional"))
    )
    (net (code "32") (name "Net-(R34-1)") (class "Default")
      (node (ref "JP12") (pin "1") (pinfunction "1_1") (pintype "passive"))
      (node (ref "R34") (pin "P$1") (pinfunction "1_P$1") (pintype "bidirectional"))
      (node (ref "U$6") (pin "1") (pinfunction "MODSEL_1") (pintype "bidirectional"))
    )
    (net (code "33") (name "Net-(R52-1)") (class "Default")
      (node (ref "JP18") (pin "1") (pinfunction "1_1") (pintype "passive"))
      (node (ref "R52") (pin "P$1") (pinfunction "1_P$1") (pintype "bidirectional"))
      (node (ref "U$11") (pin "1") (pinfunction "MODSEL_1") (pintype "bidirectional"))
    )
    (net (code "34") (name "Net-(U$1-LINN)") (class "Default")
      (node (ref "C27") (pin "2") (pinfunction "2_2") (pintype "passive"))
      (node (ref "U$1") (pin "11") (pinfunction "LINN_11") (pintype "bidirectional"))
    )
    (net (code "35") (name "Net-(U$1-LINP)") (class "Default")
      (node (ref "C26") (pin "2") (pinfunction "2_2") (pintype "passive"))
      (node (ref "U$1") (pin "10") (pinfunction "LINP_10") (pintype "bidirectional"))
    )
    (net (code "36") (name "Net-(U$1-RINN)") (class "Default")
      (node (ref "C25") (pin "2") (pinfunction "2_2") (pintype "passive"))
      (node (ref "U$1") (pin "5") (pinfunction "RINN_5") (pintype "bidirectional"))
    )
    (net (code "37") (name "Net-(U$1-RINP)") (class "Default")
      (node (ref "C24") (pin "2") (pinfunction "2_2") (pintype "passive"))
      (node (ref "U$1") (pin "4") (pinfunction "RINP_4") (pintype "bidirectional"))
    )
    (net (code "38") (name "Net-(U$6-LINN)") (class "Default")
      (node (ref "C56") (pin "2") (pinfunction "2_2") (pintype "passive"))
      (node (ref "U$6") (pin "11") (pinfunction "LINN_11") (pintype "bidirectional"))
    )
    (net (code "39") (name "Net-(U$6-LINP)") (class "Default")
      (node (ref "C55") (pin "2") (pinfunction "2_2") (pintype "passive"))
      (node (ref "U$6") (pin "10") (pinfunction "LINP_10") (pintype "bidirectional"))
    )
    (net (code "40") (name "Net-(U$6-RINN)") (class "Default")
      (node (ref "C54") (pin "2") (pinfunction "2_2") (pintype "passive"))
      (node (ref "U$6") (pin "5") (pinfunction "RINN_5") (pintype "bidirectional"))
    )
    (net (code "41") (name "Net-(U$6-RINP)") (class "Default")
      (node (ref "C53") (pin "2") (pinfunction "2_2") (pintype "passive"))
      (node (ref "U$6") (pin "4") (pinfunction "RINP_4") (pintype "bidirectional"))
    )
    (net (code "42") (name "Net-(U$11-RINN)") (class "Default")
      (node (ref "C83") (pin "2") (pinfunction "2_2") (pintype "passive"))
      (node (ref "U$11") (pin "5") (pinfunction "RINN_5") (pintype "bidirectional"))
    )
    (net (code "43") (name "Net-(U$11-RINP)") (class "Default")
      (node (ref "C82") (pin "2") (pinfunction "2_2") (pintype "passive"))
      (node (ref "U$11") (pin "4") (pinfunction "RINP_4") (pintype "bidirectional"))
    )
    (net (code "44") (name "PVCC") (class "Default")
      (node (ref "C10") (pin "P$1") (pinfunction "1_P$1") (pintype "bidirectional"))
      (node (ref "C11") (pin "P$1") (pinfunction "1_P$1") (pintype "bidirectional"))
      (node (ref "C12") (pin "P$1") (pinfunction "1_P$1") (pintype "bidirectional"))
      (node (ref "C13") (pin "+") (pinfunction "+_+") (pintype "passive"))
      (node (ref "C14") (pin "+") (pinfunction "+_+") (pintype "passive"))
      (node (ref "C38") (pin "P$1") (pinfunction "1_P$1") (pintype "bidirectional"))
      (node (ref "C39") (pin "P$1") (pinfunction "1_P$1") (pintype "bidirectional"))
      (node (ref "C40") (pin "P$1") (pinfunction "1_P$1") (pintype "bidirectional"))
      (node (ref "C41") (pin "P$1") (pinfunction "1_P$1") (pintype "bidirectional"))
      (node (ref "C42") (pin "+") (pinfunction "+_+") (pintype "passive"))
      (node (ref "C43") (pin "+") (pinfunction "+_+") (pintype "passive"))
      (node (ref "C67") (pin "P$1") (pinfunction "1_P$1") (pintype "bidirectional"))
      (node (ref "C68") (pin "P$1") (pinfunction "1_P$1") (pintype "bidirectional"))
      (node (ref "C69") (pin "P$1") (pinfunction "1_P$1") (pintype "bidirectional"))
      (node (ref "C70") (pin "P$1") (pinfunction "1_P$1") (pintype "bidirectional"))
      (node (ref "C71") (pin "+") (pinfunction "+_+") (pintype "passive"))
      (node (ref "C72") (pin "+") (pinfunction "+_+") (pintype "passive"))
      (node (ref "C9") (pin "P$1") (pinfunction "1_P$1") (pintype "bidirectional"))
      (node (ref "CON3") (pin "2") (pinfunction "2_2") (pintype "bidirectional"))
      (node (ref "R27") (pin "P$1") (pinfunction "1_P$1") (pintype "bidirectional"))
      (node (ref "R34") (pin "P$2") (pinfunction "2_P$2") (pintype "bidirectional"))
      (node (ref "R35") (pin "P$2") (pinfunction "2_P$2") (pintype "bidirectional"))
      (node (ref "R36") (pin "P$2") (pinfunction "2_P$2") (pintype "bidirectional"))
      (node (ref "R45") (pin "P$1") (pinfunction "1_P$1") (pintype "bidirectional"))
      (node (ref "R52") (pin "P$2") (pinfunction "2_P$2") (pintype "bidirectional"))
      (node (ref "R53") (pin "P$2") (pinfunction "2_P$2") (pintype "bidirectional"))
      (node (ref "R54") (pin "P$2") (pinfunction "2_P$2") (pintype "bidirectional"))
      (node (ref "U$1") (pin "17") (pinfunction "AVCC_17") (pintype "bidirectional"))
      (node (ref "U$1") (pin "18") (pinfunction "PVCC_18") (pintype "bidirectional"))
      (node (ref "U$1") (pin "19") (pinfunction "PVCC_19") (pintype "bidirectional"))
      (node (ref "U$1") (pin "31") (pinfunction "PVCC_31") (pintype "bidirectional"))
      (node (ref "U$1") (pin "32") (pinfunction "PVCC_32") (pintype "bidirectional"))
      (node (ref "U$11") (pin "17") (pinfunction "AVCC_17") (pintype "bidirectional"))
      (node (ref "U$11") (pin "18") (pinfunction "PVCC_18") (pintype "bidirectional"))
      (node (ref "U$11") (pin "19") (pinfunction "PVCC_19") (pintype "bidirectional"))
      (node (ref "U$11") (pin "31") (pinfunction "PVCC_31") (pintype "bidirectional"))
      (node (ref "U$11") (pin "32") (pinfunction "PVCC_32") (pintype "bidirectional"))
      (node (ref "U$6") (pin "17") (pinfunction "AVCC_17") (pintype "bidirectional"))
      (node (ref "U$6") (pin "18") (pinfunction "PVCC_18") (pintype "bidirectional"))
      (node (ref "U$6") (pin "19") (pinfunction "PVCC_19") (pintype "bidirectional"))
      (node (ref "U$6") (pin "31") (pinfunction "PVCC_31") (pintype "bidirectional"))
      (node (ref "U$6") (pin "32") (pinfunction "PVCC_32") (pintype "bidirectional"))
    )
    (net (code "45") (name "REAR_BSNL") (class "Default")
      (node (ref "C50") (pin "P$1") (pinfunction "1_P$1") (pintype "bidirectional"))
      (node (ref "U$6") (pin "20") (pinfunction "BSNL_20") (pintype "bidirectional"))
    )
    (net (code "46") (name "REAR_BSNR") (class "Default")
      (node (ref "C46") (pin "P$1") (pinfunction "1_P$1") (pintype "bidirectional"))
      (node (ref "U$6") (pin "26") (pinfunction "BSNR_26") (pintype "bidirectional"))
    )
    (net (code "47") (name "REAR_BSPL") (class "Default")
      (node (ref "C48") (pin "P$1") (pinfunction "1_P$1") (pintype "bidirectional"))
      (node (ref "U$6") (pin "24") (pinfunction "BSPL_24") (pintype "bidirectional"))
    )
    (net (code "48") (name "REAR_BSPR") (class "Default")
      (node (ref "C44") (pin "P$1") (pinfunction "1_P$1") (pintype "bidirectional"))
      (node (ref "U$6") (pin "30") (pinfunction "BSPR_30") (pintype "bidirectional"))
    )
    (net (code "49") (name "REAR_LEFT+") (class "Default")
      (node (ref "C32") (pin "1") (pinfunction "1_1") (pintype "bidirectional"))
      (node (ref "CON6") (pin "2") (pinfunction "2_2") (pintype "bidirectional"))
      (node (ref "U$9") (pin "2") (pinfunction "2_2") (pintype "bidirectional"))
    )
    (net (code "50") (name "REAR_LEFT-") (class "Default")
      (node (ref "C33") (pin "1") (pinfunction "1_1") (pintype "bidirectional"))
      (node (ref "CON6") (pin "1") (pinfunction "1_1") (pintype "bidirectional"))
      (node (ref "U$10") (pin "2") (pinfunction "2_2") (pintype "bidirectional"))
    )
    (net (code "51") (name "REAR_OUTNL") (class "Default")
      (node (ref "C50") (pin "P$2") (pinfunction "2_P$2") (pintype "bidirectional"))
      (node (ref "U$10") (pin "1") (pinfunction "1_1") (pintype "bidirectional"))
      (node (ref "U$6") (pin "21") (pinfunction "OUTNL_21") (pintype "bidirectional"))
    )
    (net (code "52") (name "REAR_OUTNR") (class "Default")
      (node (ref "C46") (pin "P$2") (pinfunction "2_P$2") (pintype "bidirectional"))
      (node (ref "U$6") (pin "27") (pinfunction "OUTNR_27") (pintype "bidirectional"))
      (node (ref "U$8") (pin "1") (pinfunction "1_1") (pintype "bidirectional"))
    )
    (net (code "53") (name "REAR_OUTPL") (class "Default")
      (node (ref "C48") (pin "P$2") (pinfunction "2_P$2") (pintype "bidirectional"))
      (node (ref "U$6") (pin "23") (pinfunction "OUTPL_23") (pintype "bidirectional"))
      (node (ref "U$9") (pin "1") (pinfunction "1_1") (pintype "bidirectional"))
    )
    (net (code "54") (name "REAR_OUTPR") (class "Default")
      (node (ref "C44") (pin "P$2") (pinfunction "2_P$2") (pintype "bidirectional"))
      (node (ref "U$6") (pin "29") (pinfunction "OUTPR_29") (pintype "bidirectional"))
      (node (ref "U$7") (pin "1") (pinfunction "1_1") (pintype "bidirectional"))
    )
    (net (code "55") (name "REAR_RIGHT+") (class "Default")
      (node (ref "C30") (pin "1") (pinfunction "1_1") (pintype "bidirectional"))
      (node (ref "CON5") (pin "2") (pinfunction "2_2") (pintype "bidirectional"))
      (node (ref "U$7") (pin "2") (pinfunction "2_2") (pintype "bidirectional"))
    )
    (net (code "56") (name "REAR_RIGHT-") (class "Default")
      (node (ref "C31") (pin "1") (pinfunction "1_1") (pintype "bidirectional"))
      (node (ref "CON5") (pin "1") (pinfunction "1_1") (pintype "bidirectional"))
      (node (ref "U$8") (pin "2") (pinfunction "2_2") (pintype "bidirectional"))
    )
    (net (code "57") (name "SYNC") (class "Default")
      (node (ref "R13") (pin "P$2") (pinfunction "2_P$2") (pintype "bidirectional"))
      (node (ref "U$1") (pin "16") (pinfunction "SYNC_16") (pintype "bidirectional"))
    )
    (net (code "58") (name "SYNC_1") (class "Default")
      (node (ref "R13") (pin "P$1") (pinfunction "1_P$1") (pintype "bidirectional"))
      (node (ref "R31") (pin "P$2") (pinfunction "2_P$2") (pintype "bidirectional"))
      (node (ref "U$6") (pin "16") (pinfunction "SYNC_16") (pintype "bidirectional"))
    )
    (net (code "59") (name "SYNC_2") (class "Default")
      (node (ref "R31") (pin "P$1") (pinfunction "1_P$1") (pintype "bidirectional"))
      (node (ref "R49") (pin "P$2") (pinfunction "2_P$2") (pintype "bidirectional"))
      (node (ref "U$11") (pin "16") (pinfunction "SYNC_16") (pintype "bidirectional"))
    )
    (net (code "60") (name "unconnected-(C24-Pad1)") (class "Default")
      (node (ref "C24") (pin "1") (pinfunction "1_1") (pintype "passive"))
    )
    (net (code "61") (name "unconnected-(C25-Pad1)") (class "Default")
      (node (ref "C25") (pin "1") (pinfunction "1_1") (pintype "passive"))
    )
    (net (code "62") (name "unconnected-(C26-Pad1)") (class "Default")
      (node (ref "C26") (pin "1") (pinfunction "1_1") (pintype "passive"))
    )
    (net (code "63") (name "unconnected-(C27-Pad1)") (class "Default")
      (node (ref "C27") (pin "1") (pinfunction "1_1") (pintype "passive"))
    )
    (net (code "64") (name "unconnected-(C53-Pad1)") (class "Default")
      (node (ref "C53") (pin "1") (pinfunction "1_1") (pintype "passive"))
    )
    (net (code "65") (name "unconnected-(C54-Pad1)") (class "Default")
      (node (ref "C54") (pin "1") (pinfunction "1_1") (pintype "passive"))
    )
    (net (code "66") (name "unconnected-(C55-Pad1)") (class "Default")
      (node (ref "C55") (pin "1") (pinfunction "1_1") (pintype "passive"))
    )
    (net (code "67") (name "unconnected-(C56-Pad1)") (class "Default")
      (node (ref "C56") (pin "1") (pinfunction "1_1") (pintype "passive"))
    )
    (net (code "68") (name "unconnected-(C82-Pad1)") (class "Default")
      (node (ref "C82") (pin "1") (pinfunction "1_1") (pintype "passive"))
    )
    (net (code "69") (name "unconnected-(C83-Pad1)") (class "Default")
      (node (ref "C83") (pin "1") (pinfunction "1_1") (pintype "passive"))
    )
  )
)
